# Probe_Connections.net
KiCad netlist of a schematic drawn in Altium Designer
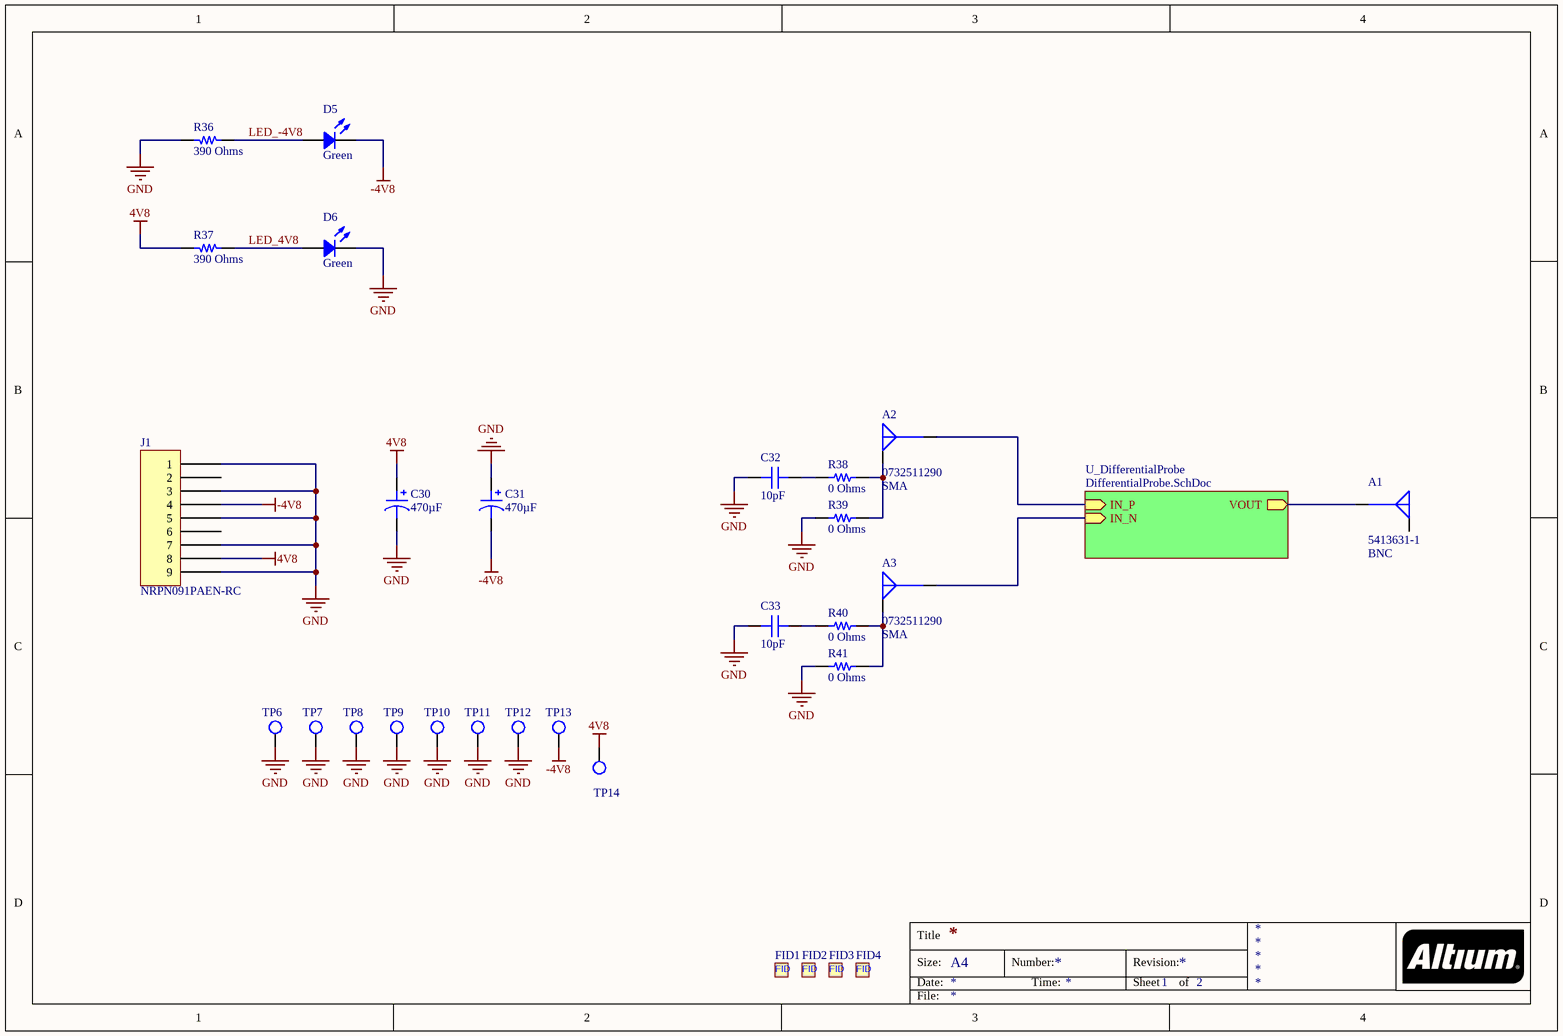
[diagram p0: Probe Connections.SchDoc]

(export (version "E")
  (design (tool "Eeschema 10.0.6"))
  (components
    (comp (ref "A1")
      (value "5413631-1")
      (footprint "TE 5413631-1")
      (description "CONN BNC JACK R/A 50 OHM PCB")
      (fields
        (field (name "CONNECTOR STYLE") "BNC")
        (field (name "MANUFACTURER") "TE Connectivity AMP Connectors")
      )
      (libsource (lib "altiumlibrary.com") (part "Basic Antenna"))
    )
    (comp (ref "A2")
      (value "0732511290")
      (footprint "MOLEX SD-73251-129")
      (description "CONN SMA JACK STR 50OHM EDGE MNT")
      (fields (field (name "CONNECTOR STYLE") "SMA") (field (name "MANUFACTURER") "Molex"))
      (libsource (lib "altiumlibrary.com") (part "Basic Antenna"))
    )
    (comp (ref "A3")
      (value "0732511290")
      (footprint "MOLEX SD-73251-129")
      (description "CONN SMA JACK STR 50OHM EDGE MNT")
      (fields (field (name "CONNECTOR STYLE") "SMA") (field (name "MANUFACTURER") "Molex"))
      (libsource (lib "altiumlibrary.com") (part "Basic Antenna"))
    )
    (comp (ref "C30")
      (value "470µF")
      (footprint "CAP POL 2917_7343")
      (description "CAP TANT 470UF 10% 10V 2917")
      (fields (field (name "PART NUMBER") "TPSE477K010R0100") (field (name "MANUFACTURER") "AVX Corporation"))
      (libsource (lib "altiumlibrary.com") (part "Polarised Capacitor"))
    )
    (comp (ref "C31")
      (value "470µF")
      (footprint "CAP POL 2917_7343")
      (description "CAP TANT 470UF 10% 10V 2917")
      (fields (field (name "PART NUMBER") "TPSE477K010R0100") (field (name "MANUFACTURER") "AVX Corporation"))
      (libsource (lib "altiumlibrary.com") (part "Polarised Capacitor"))
    )
    (comp (ref "C32")
      (value "10pF")
      (footprint "CAP 1206_3216 - 1.0MM")
      (description "CAP CER 10PF 2KV C0G/NP0 1206")
      (fields (field (name "PART NUMBER") "1206GA100JAT2A") (field (name "MANUFACTURER") "AVX Corporation"))
      (libsource (lib "altiumlibrary.com") (part "Capacitor"))
    )
    (comp (ref "C33")
      (value "10pF")
      (footprint "CAP 1206_3216 - 1.0MM")
      (description "CAP CER 10PF 2KV C0G/NP0 1206")
      (fields (field (name "PART NUMBER") "1206GA100JAT2A") (field (name "MANUFACTURER") "AVX Corporation"))
      (libsource (lib "altiumlibrary.com") (part "Capacitor"))
    )
    (comp (ref "D5")
      (value "Green")
      (footprint "LED 0805_2012 GREEN")
      (description "LED GREEN CLEAR CHIP SMD")
      (fields (field (name "PART NUMBER") "APHCM2012CGCK-F01") (field (name "MANUFACTURER") "Kingbright"))
      (libsource (lib "altiumlibrary.com") (part "LED"))
    )
    (comp (ref "D6")
      (value "Green")
      (footprint "LED 0805_2012 GREEN")
      (description "LED GREEN CLEAR CHIP SMD")
      (fields (field (name "PART NUMBER") "APHCM2012CGCK-F01") (field (name "MANUFACTURER") "Kingbright"))
      (libsource (lib "altiumlibrary.com") (part "LED"))
    )
    (comp (ref "FID1")
      (value "Fiducial")
      (footprint "Fiducial-1mm")
      (libsource (lib "Original Circuit") (part "Fiducial"))
    )
    (comp (ref "FID2")
      (value "Fiducial")
      (footprint "Fiducial-1mm")
      (libsource (lib "Original Circuit") (part "Fiducial"))
    )
    (comp (ref "FID3")
      (value "Fiducial")
      (footprint "Fiducial-1mm")
      (libsource (lib "Original Circuit") (part "Fiducial"))
    )
    (comp (ref "FID4")
      (value "Fiducial")
      (footprint "Fiducial-1mm")
      (libsource (lib "Original Circuit") (part "Fiducial"))
    )
    (comp (ref "J1")
      (value "NRPN091PAEN-RC")
      (footprint "SULLINS NRPN091PAEN-RC")
      (description "CONN HEADER VERT 9POS 2MM")
      (fields (field (name "MANUFACTURER") "Sullins Connector Solutions"))
      (libsource (lib "altiumlibrary.com") (part "9 Pin"))
    )
    (comp (ref "R36")
      (value "390 Ohms")
      (footprint "RES 0805_2012")
      (description "RES SMD 390 OHM 1% 1/8W 0805")
      (fields
        (field (name "PART NUMBER") "CRG0805F390R")
        (field (name "MANUFACTURER") "TE Connectivity Passive Product")
      )
      (libsource (lib "altiumlibrary.com") (part "Resistor"))
    )
    (comp (ref "R37")
      (value "390 Ohms")
      (footprint "RES 0805_2012")
      (description "RES SMD 390 OHM 1% 1/8W 0805")
      (fields
        (field (name "PART NUMBER") "CRG0805F390R")
        (field (name "MANUFACTURER") "TE Connectivity Passive Product")
      )
      (libsource (lib "altiumlibrary.com") (part "Resistor"))
    )
    (comp (ref "R38")
      (value "0 Ohms")
      (footprint "RES 1206_3216")
      (description "RES 0 OHM JUMPER 1/4W 1206")
      (fields (field (name "PART NUMBER") "RC1206JR-100RL") (field (name "MANUFACTURER") "Yageo"))
      (libsource (lib "altiumlibrary.com") (part "Resistor"))
    )
    (comp (ref "R39")
      (value "0 Ohms")
      (footprint "RES 1206_3216")
      (description "RES 0 OHM JUMPER 1/4W 1206")
      (fields (field (name "PART NUMBER") "RC1206JR-100RL") (field (name "MANUFACTURER") "Yageo"))
      (libsource (lib "altiumlibrary.com") (part "Resistor"))
    )
    (comp (ref "R40")
      (value "0 Ohms")
      (footprint "RES 1206_3216")
      (description "RES 0 OHM JUMPER 1/4W 1206")
      (fields (field (name "PART NUMBER") "RC1206JR-100RL") (field (name "MANUFACTURER") "Yageo"))
      (libsource (lib "altiumlibrary.com") (part "Resistor"))
    )
    (comp (ref "R41")
      (value "0 Ohms")
      (footprint "RES 1206_3216")
      (description "RES 0 OHM JUMPER 1/4W 1206")
      (fields (field (name "PART NUMBER") "RC1206JR-100RL") (field (name "MANUFACTURER") "Yageo"))
      (libsource (lib "altiumlibrary.com") (part "Resistor"))
    )
    (comp (ref "TP6")
      (value "Test Point")
      (footprint "TestPoint-1.5mm")
      (libsource (lib "Original Circuit") (part "Test Point"))
    )
    (comp (ref "TP7")
      (value "Test Point")
      (footprint "TestPoint-1.5mm")
      (libsource (lib "Original Circuit") (part "Test Point"))
    )
    (comp (ref "TP8")
      (value "Test Point")
      (footprint "TestPoint-1.5mm")
      (libsource (lib "Original Circuit") (part "Test Point"))
    )
    (comp (ref "TP9")
      (value "Test Point")
      (footprint "TestPoint-1.5mm")
      (libsource (lib "Original Circuit") (part "Test Point"))
    )
    (comp (ref "TP10")
      (value "Test Point")
      (footprint "TestPoint-1.5mm")
      (libsource (lib "Original Circuit") (part "Test Point"))
    )
    (comp (ref "TP11")
      (value "Test Point")
      (footprint "TestPoint-1.5mm")
      (libsource (lib "Original Circuit") (part "Test Point"))
    )
    (comp (ref "TP12")
      (value "Test Point")
      (footprint "TestPoint-1.5mm")
      (libsource (lib "Original Circuit") (part "Test Point"))
    )
    (comp (ref "TP13")
      (value "Test Point")
      (footprint "TestPoint-1.5mm")
      (libsource (lib "Original Circuit") (part "Test Point"))
    )
    (comp (ref "TP14")
      (value "Test Point")
      (footprint "TestPoint-1.5mm")
      (libsource (lib "Original Circuit") (part "Test Point"))
    )
  )
  (nets
    (net (code "1") (name "-4V8") (class "Default")
      (node (ref "C31") (pin "2") (pinfunction "2_2") (pintype "passive"))
      (node (ref "D5") (pin "2") (pinfunction "2_2") (pintype "passive"))
      (node (ref "J1") (pin "4") (pinfunction "4_4") (pintype "passive"))
      (node (ref "TP13") (pin "1") (pinfunction "TP_1") (pintype "passive"))
    )
    (net (code "2") (name "/IN_N") (class "Default")
      (node (ref "A3") (pin "S") (pinfunction "S_S") (pintype "passive"))
    )
    (net (code "3") (name "/IN_P") (class "Default")
      (node (ref "A2") (pin "S") (pinfunction "S_S") (pintype "passive"))
    )
    (net (code "4") (name "/LED_-4V8") (class "Default")
      (node (ref "D5") (pin "1") (pinfunction "1_1") (pintype "passive"))
      (node (ref "R36") (pin "1") (pinfunction "1_1") (pintype "passive"))
    )
    (net (code "5") (name "/LED_4V8") (class "Default")
      (node (ref "D6") (pin "1") (pinfunction "1_1") (pintype "passive"))
      (node (ref "R37") (pin "1") (pinfunction "1_1") (pintype "passive"))
    )
    (net (code "6") (name "/VOUT") (class "Default")
      (node (ref "A1") (pin "S") (pinfunction "S_S") (pintype "passive"))
    )
    (net (code "7") (name "4V8") (class "Default")
      (node (ref "C30") (pin "1") (pinfunction "1_1") (pintype "passive"))
      (node (ref "J1") (pin "8") (pinfunction "8_8") (pintype "passive"))
      (node (ref "R37") (pin "2") (pinfunction "2_2") (pintype "passive"))
      (node (ref "TP14") (pin "1") (pinfunction "TP_1") (pintype "passive"))
    )
    (net (code "8") (name "GND") (class "Default")
      (node (ref "C30") (pin "2") (pinfunction "2_2") (pintype "passive"))
      (node (ref "C31") (pin "1") (pinfunction "1_1") (pintype "passive"))
      (node (ref "C32") (pin "1") (pinfunction "1_1") (pintype "passive"))
      (node (ref "C33") (pin "1") (pinfunction "1_1") (pintype "passive"))
      (node (ref "D6") (pin "2") (pinfunction "2_2") (pintype "passive"))
      (node (ref "J1") (pin "1") (pinfunction "1_1") (pintype "passive"))
      (node (ref "J1") (pin "3") (pinfunction "3_3") (pintype "passive"))
      (node (ref "J1") (pin "5") (pinfunction "5_5") (pintype "passive"))
      (node (ref "J1") (pin "7") (pinfunction "7_7") (pintype "passive"))
      (node (ref "J1") (pin "9") (pinfunction "9_9") (pintype "passive"))
      (node (ref "R36") (pin "2") (pinfunction "2_2") (pintype "passive"))
      (node (ref "R39") (pin "1") (pinfunction "1_1") (pintype "passive"))
      (node (ref "R41") (pin "1") (pinfunction "1_1") (pintype "passive"))
      (node (ref "TP10") (pin "1") (pinfunction "TP_1") (pintype "passive"))
      (node (ref "TP11") (pin "1") (pinfunction "TP_1") (pintype "passive"))
      (node (ref "TP12") (pin "1") (pinfunction "TP_1") (pintype "passive"))
      (node (ref "TP6") (pin "1") (pinfunction "TP_1") (pintype "passive"))
      (node (ref "TP7") (pin "1") (pinfunction "TP_1") (pintype "passive"))
      (node (ref "TP8") (pin "1") (pinfunction "TP_1") (pintype "passive"))
      (node (ref "TP9") (pin "1") (pinfunction "TP_1") (pintype "passive"))
    )
    (net (code "9") (name "Net-(A2-PadG)") (class "Default")
      (node (ref "A2") (pin "G") (pinfunction "G_G") (pintype "passive"))
      (node (ref "R38") (pin "2") (pinfunction "2_2") (pintype "passive"))
      (node (ref "R39") (pin "2") (pinfunction "2_2") (pintype "passive"))
    )
    (net (code "10") (name "Net-(A3-PadG)") (class "Default")
      (node (ref "A3") (pin "G") (pinfunction "G_G") (pintype "passive"))
      (node (ref "R40") (pin "2") (pinfunction "2_2") (pintype "passive"))
      (node (ref "R41") (pin "2") (pinfunction "2_2") (pintype "passive"))
    )
    (net (code "11") (name "Net-(C32-Pad2)") (class "Default")
      (node (ref "C32") (pin "2") (pinfunction "2_2") (pintype "passive"))
      (node (ref "R38") (pin "1") (pinfunction "1_1") (pintype "passive"))
    )
    (net (code "12") (name "Net-(C33-Pad2)") (class "Default")
      (node (ref "C33") (pin "2") (pinfunction "2_2") (pintype "passive"))
      (node (ref "R40") (pin "1") (pinfunction "1_1") (pintype "passive"))
    )
    (net (code "13") (name "unconnected-(A1-PadG)") (class "Default")
      (node (ref "A1") (pin "G") (pinfunction "G_G") (pintype "passive"))
    )
    (net (code "14") (name "unconnected-(J1-Pad2)") (class "Default")
      (node (ref "J1") (pin "2") (pinfunction "2_2") (pintype "passive"))
    )
    (net (code "15") (name "unconnected-(J1-Pad6)") (class "Default")
      (node (ref "J1") (pin "6") (pinfunction "6_6") (pintype "passive"))
    )
  )
)
